# buck.net
KiCad netlist of a schematic drawn in Altium Designer
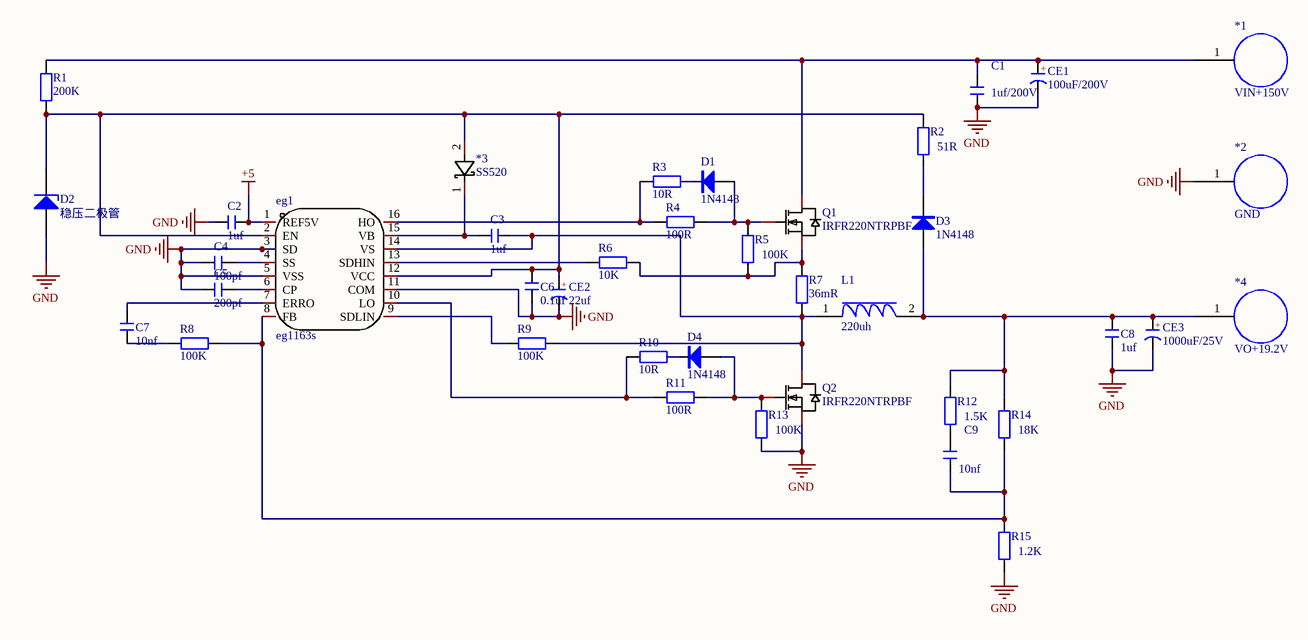
[diagram p0: buck.SchDoc]

(export (version "E")
  (design (tool "Eeschema 10.0.6"))
  (components
    (comp (ref "*1") (value "VIN+150V") (footprint "焊盘接口") (libsource (lib "buck") (part "焊盘接口")))
    (comp (ref "*2") (value "GND") (footprint "焊盘接口") (libsource (lib "buck") (part "焊盘接口")))
    (comp (ref "*3") (value "SS520") (footprint "SS520") (libsource (lib "buck") (part "SS520")))
    (comp (ref "*4") (value "VO+19.2V") (footprint "焊盘接口") (libsource (lib "buck") (part "焊盘接口")))
    (comp (ref "C1")
      (value "1uf/200V")
      (footprint "C 0603_L")
      (description "贴片电容")
      (libsource (lib "0.1 - 电阻-电容-电感") (part "C"))
    )
    (comp (ref "C2")
      (value "1uf")
      (footprint "C 0603_L")
      (description "贴片电容")
      (libsource (lib "0.1 - 电阻-电容-电感") (part "C"))
    )
    (comp (ref "C3")
      (value "1uf")
      (footprint "C 0603_L")
      (description "贴片电容")
      (libsource (lib "0.1 - 电阻-电容-电感") (part "C"))
    )
    (comp (ref "C4")
      (value "100pf")
      (footprint "C 0603_L")
      (description "贴片电容")
      (libsource (lib "0.1 - 电阻-电容-电感") (part "C"))
    )
    (comp (ref "C5")
      (value "200pf")
      (footprint "C 0603_L")
      (description "贴片电容")
      (libsource (lib "0.1 - 电阻-电容-电感") (part "C"))
    )
    (comp (ref "C6")
      (value "0.1uf")
      (footprint "C 0603_L")
      (description "贴片电容")
      (libsource (lib "0.1 - 电阻-电容-电感") (part "C"))
    )
    (comp (ref "C7")
      (value "10nf")
      (footprint "C 0603_L")
      (description "贴片电容")
      (libsource (lib "0.1 - 电阻-电容-电感") (part "C"))
    )
    (comp (ref "C8")
      (value "1uf")
      (footprint "C 0603_L")
      (description "贴片电容")
      (libsource (lib "0.1 - 电阻-电容-电感") (part "C"))
    )
    (comp (ref "C9")
      (value "10nf")
      (footprint "C 0603_L")
      (description "贴片电容")
      (libsource (lib "0.1 - 电阻-电容-电感") (part "C"))
    )
    (comp (ref "CE1")
      (value "100uF/200V")
      (footprint "CAP 10*22*40 - GD")
      (description "直插电解电容")
      (libsource (lib "0.1 - 电阻-电容-电感") (part "CE"))
    )
    (comp (ref "CE2")
      (value "22uf")
      (footprint "CAP 10*22*31.5")
      (description "直插电解电容")
      (libsource (lib "0.1 - 电阻-电容-电感") (part "CE"))
    )
    (comp (ref "CE3")
      (value "1000uF/25V")
      (footprint "CAP 10*22*31.5")
      (description "直插电解电容")
      (libsource (lib "0.1 - 电阻-电容-电感") (part "CE"))
    )
    (comp (ref "D1")
      (value "1N4148")
      (footprint "MINI_MELF (LL34)")
      (description "开关二极管")
      (libsource (lib "0.2 - 二极管-整流桥") (part "1N4148"))
    )
    (comp (ref "D2")
      (value "稳压二极管")
      (footprint "SOD-123")
      (description "Zener Diode")
      (libsource (lib "0.2 - 二极管-整流桥") (part "稳压二极管"))
    )
    (comp (ref "D3")
      (value "1N4148")
      (footprint "MINI_MELF (LL34)")
      (description "开关二极管")
      (libsource (lib "0.2 - 二极管-整流桥") (part "1N4148"))
    )
    (comp (ref "D4")
      (value "1N4148")
      (footprint "MINI_MELF (LL34)")
      (description "开关二极管")
      (libsource (lib "0.2 - 二极管-整流桥") (part "1N4148"))
    )
    (comp (ref "eg1") (value "eg1163s") (footprint "eg1163S") (libsource (lib "Schlib1") (part "eg1163s")))
    (comp (ref "L1") (value "220uh") (footprint "电感") (libsource (lib "buck") (part "电感")))
    (comp (ref "Q1")
      (value "IRFR220NTRPBF")
      (footprint "IRFR220NTRPBF")
      (fields (field (name "MANUFACTURER") "Infineon(英飞凌)") (field (name "NAME") "IRFR220NTRPBF"))
      (libsource (lib "buck") (part "IRFR220NTRPBF"))
    )
    (comp (ref "Q2")
      (value "IRFR220NTRPBF")
      (footprint "IRFR220NTRPBF")
      (fields (field (name "MANUFACTURER") "Infineon(英飞凌)") (field (name "NAME") "IRFR220NTRPBF"))
      (libsource (lib "buck") (part "IRFR220NTRPBF"))
    )
    (comp (ref "R1")
      (value "200K")
      (footprint "RES 0603")
      (description "贴片电阻")
      (fields (field (name "版权归属") "来自淘宝 ID：黄晶宝石"))
      (libsource (lib "0.1 - 电阻-电容-电感") (part "R"))
    )
    (comp (ref "R2")
      (value "51R")
      (footprint "RES 0603")
      (description "贴片电阻")
      (fields (field (name "版权归属") "来自淘宝 ID：黄晶宝石"))
      (libsource (lib "0.1 - 电阻-电容-电感") (part "R"))
    )
    (comp (ref "R3")
      (value "10R")
      (footprint "RES 0603")
      (description "贴片电阻")
      (fields (field (name "版权归属") "来自淘宝 ID：黄晶宝石"))
      (libsource (lib "0.1 - 电阻-电容-电感") (part "R"))
    )
    (comp (ref "R4")
      (value "100R")
      (footprint "RES 0603")
      (description "贴片电阻")
      (fields (field (name "版权归属") "来自淘宝 ID：黄晶宝石"))
      (libsource (lib "0.1 - 电阻-电容-电感") (part "R"))
    )
    (comp (ref "R5")
      (value "100K")
      (footprint "RES 0603")
      (description "贴片电阻")
      (fields (field (name "版权归属") "来自淘宝 ID：黄晶宝石"))
      (libsource (lib "0.1 - 电阻-电容-电感") (part "R"))
    )
    (comp (ref "R6")
      (value "10K")
      (footprint "RES 0603")
      (description "贴片电阻")
      (fields (field (name "版权归属") "来自淘宝 ID：黄晶宝石"))
      (libsource (lib "0.1 - 电阻-电容-电感") (part "R"))
    )
    (comp (ref "R7")
      (value "36mR")
      (footprint "RES 0603")
      (description "贴片电阻")
      (fields (field (name "版权归属") "来自淘宝 ID：黄晶宝石"))
      (libsource (lib "0.1 - 电阻-电容-电感") (part "R"))
    )
    (comp (ref "R8")
      (value "100K")
      (footprint "RES 0603")
      (description "贴片电阻")
      (fields (field (name "版权归属") "来自淘宝 ID：黄晶宝石"))
      (libsource (lib "0.1 - 电阻-电容-电感") (part "R"))
    )
    (comp (ref "R9")
      (value "100K")
      (footprint "RES 0603")
      (description "贴片电阻")
      (fields (field (name "版权归属") "来自淘宝 ID：黄晶宝石"))
      (libsource (lib "0.1 - 电阻-电容-电感") (part "R"))
    )
    (comp (ref "R10")
      (value "10R")
      (footprint "RES 0603")
      (description "贴片电阻")
      (fields (field (name "版权归属") "来自淘宝 ID：黄晶宝石"))
      (libsource (lib "0.1 - 电阻-电容-电感") (part "R"))
    )
    (comp (ref "R11")
      (value "100R")
      (footprint "RES 0603")
      (description "贴片电阻")
      (fields (field (name "版权归属") "来自淘宝 ID：黄晶宝石"))
      (libsource (lib "0.1 - 电阻-电容-电感") (part "R"))
    )
    (comp (ref "R12")
      (value "1.5K")
      (footprint "RES 0603")
      (description "贴片电阻")
      (fields (field (name "版权归属") "来自淘宝 ID：黄晶宝石"))
      (libsource (lib "0.1 - 电阻-电容-电感") (part "R"))
    )
    (comp (ref "R13")
      (value "100K")
      (footprint "RES 0603")
      (description "贴片电阻")
      (fields (field (name "版权归属") "来自淘宝 ID：黄晶宝石"))
      (libsource (lib "0.1 - 电阻-电容-电感") (part "R"))
    )
    (comp (ref "R14")
      (value "18K")
      (footprint "RES 0603")
      (description "贴片电阻")
      (fields (field (name "版权归属") "来自淘宝 ID：黄晶宝石"))
      (libsource (lib "0.1 - 电阻-电容-电感") (part "R"))
    )
    (comp (ref "R15")
      (value "1.2K")
      (footprint "RES 0603")
      (description "贴片电阻")
      (fields (field (name "版权归属") "来自淘宝 ID：黄晶宝石"))
      (libsource (lib "0.1 - 电阻-电容-电感") (part "R"))
    )
  )
  (nets
    (net (code "1") (name "+5") (class "Default")
      (node (ref "C2") (pin "2") (pinfunction "2_2") (pintype "passive"))
      (node (ref "eg1") (pin "1") (pinfunction "REF5V_1") (pintype "passive"))
    )
    (net (code "2") (name "GND") (class "Default")
      (node (ref "*2") (pin "1") (pinfunction "1_1") (pintype "passive"))
      (node (ref "C1") (pin "1") (pinfunction "1_1") (pintype "passive"))
      (node (ref "C2") (pin "1") (pinfunction "1_1") (pintype "passive"))
      (node (ref "C4") (pin "1") (pinfunction "1_1") (pintype "passive"))
      (node (ref "C5") (pin "1") (pinfunction "1_1") (pintype "passive"))
      (node (ref "C6") (pin "2") (pinfunction "2_2") (pintype "passive"))
      (node (ref "C8") (pin "1") (pinfunction "1_1") (pintype "passive"))
      (node (ref "CE1") (pin "2") (pinfunction "K_2") (pintype "passive"))
      (node (ref "CE2") (pin "2") (pinfunction "K_2") (pintype "passive"))
      (node (ref "CE3") (pin "2") (pinfunction "K_2") (pintype "passive"))
      (node (ref "D2") (pin "1") (pinfunction "A_1") (pintype "passive"))
      (node (ref "Q2") (pin "3") (pinfunction "S_3") (pintype "passive"))
      (node (ref "R13") (pin "2") (pinfunction "2_2") (pintype "passive"))
      (node (ref "R15") (pin "2") (pinfunction "2_2") (pintype "passive"))
      (node (ref "eg1") (pin "11") (pinfunction "COM_11") (pintype "passive"))
      (node (ref "eg1") (pin "3") (pinfunction "SD_3") (pintype "passive"))
      (node (ref "eg1") (pin "5") (pinfunction "VSS_5") (pintype "passive"))
    )
    (net (code "3") (name "Net-(*3-A)") (class "Default")
      (node (ref "*3") (pin "2") (pinfunction "A_2") (pintype "passive"))
      (node (ref "C6") (pin "1") (pinfunction "1_1") (pintype "passive"))
      (node (ref "CE2") (pin "1") (pinfunction "A_1") (pintype "passive"))
      (node (ref "D2") (pin "2") (pinfunction "K_2") (pintype "passive"))
      (node (ref "R1") (pin "1") (pinfunction "1_1") (pintype "passive"))
      (node (ref "R2") (pin "1") (pinfunction "1_1") (pintype "passive"))
      (node (ref "eg1") (pin "12") (pinfunction "VCC_12") (pintype "passive"))
      (node (ref "eg1") (pin "2") (pinfunction "EN_2") (pintype "passive"))
    )
    (net (code "4") (name "Net-(*3-K)") (class "Default")
      (node (ref "*3") (pin "1") (pinfunction "K_1") (pintype "passive"))
      (node (ref "C3") (pin "2") (pinfunction "2_2") (pintype "passive"))
      (node (ref "eg1") (pin "15") (pinfunction "VB_15") (pintype "passive"))
    )
    (net (code "5") (name "Net-(C7-Pad1)") (class "Default")
      (node (ref "C7") (pin "1") (pinfunction "1_1") (pintype "passive"))
      (node (ref "R8") (pin "2") (pinfunction "2_2") (pintype "passive"))
    )
    (net (code "6") (name "Net-(C9-Pad2)") (class "Default")
      (node (ref "C9") (pin "2") (pinfunction "2_2") (pintype "passive"))
      (node (ref "R12") (pin "2") (pinfunction "2_2") (pintype "passive"))
    )
    (net (code "7") (name "Net-(CE1-A)") (class "Default")
      (node (ref "*1") (pin "1") (pinfunction "1_1") (pintype "passive"))
      (node (ref "C1") (pin "2") (pinfunction "2_2") (pintype "passive"))
      (node (ref "CE1") (pin "1") (pinfunction "A_1") (pintype "passive"))
      (node (ref "Q1") (pin "2") (pinfunction "D_2") (pintype "passive"))
      (node (ref "R1") (pin "2") (pinfunction "2_2") (pintype "passive"))
    )
    (net (code "8") (name "Net-(CE3-A)") (class "Default")
      (node (ref "*4") (pin "1") (pinfunction "1_1") (pintype "passive"))
      (node (ref "C8") (pin "2") (pinfunction "2_2") (pintype "passive"))
      (node (ref "CE3") (pin "1") (pinfunction "A_1") (pintype "passive"))
      (node (ref "D3") (pin "1") (pinfunction "A_1") (pintype "passive"))
      (node (ref "L1") (pin "2") (pinfunction "2_2") (pintype "passive"))
      (node (ref "R12") (pin "1") (pinfunction "1_1") (pintype "passive"))
      (node (ref "R14") (pin "1") (pinfunction "1_1") (pintype "passive"))
    )
    (net (code "9") (name "Net-(D1-A)") (class "Default")
      (node (ref "D1") (pin "1") (pinfunction "A_1") (pintype "passive"))
      (node (ref "Q1") (pin "1") (pinfunction "G_1") (pintype "passive"))
      (node (ref "R4") (pin "1") (pinfunction "1_1") (pintype "passive"))
      (node (ref "R5") (pin "1") (pinfunction "1_1") (pintype "passive"))
    )
    (net (code "10") (name "Net-(D1-K)") (class "Default")
      (node (ref "D1") (pin "2") (pinfunction "K_2") (pintype "passive"))
      (node (ref "R3") (pin "1") (pinfunction "1_1") (pintype "passive"))
    )
    (net (code "11") (name "Net-(D3-K)") (class "Default")
      (node (ref "D3") (pin "2") (pinfunction "K_2") (pintype "passive"))
      (node (ref "R2") (pin "2") (pinfunction "2_2") (pintype "passive"))
    )
    (net (code "12") (name "Net-(D4-A)") (class "Default")
      (node (ref "D4") (pin "1") (pinfunction "A_1") (pintype "passive"))
      (node (ref "Q2") (pin "1") (pinfunction "G_1") (pintype "passive"))
      (node (ref "R11") (pin "1") (pinfunction "1_1") (pintype "passive"))
      (node (ref "R13") (pin "1") (pinfunction "1_1") (pintype "passive"))
    )
    (net (code "13") (name "Net-(D4-K)") (class "Default")
      (node (ref "D4") (pin "2") (pinfunction "K_2") (pintype "passive"))
      (node (ref "R10") (pin "1") (pinfunction "1_1") (pintype "passive"))
    )
    (net (code "14") (name "Net-(Q1-S)") (class "Default")
      (node (ref "Q1") (pin "3") (pinfunction "S_3") (pintype "passive"))
      (node (ref "R5") (pin "2") (pinfunction "2_2") (pintype "passive"))
      (node (ref "R6") (pin "1") (pinfunction "1_1") (pintype "passive"))
      (node (ref "R7") (pin "1") (pinfunction "1_1") (pintype "passive"))
    )
    (net (code "15") (name "Net-(Q2-D)") (class "Default")
      (node (ref "C3") (pin "1") (pinfunction "1_1") (pintype "passive"))
      (node (ref "L1") (pin "1") (pinfunction "1_1") (pintype "passive"))
      (node (ref "Q2") (pin "2") (pinfunction "D_2") (pintype "passive"))
      (node (ref "R7") (pin "2") (pinfunction "2_2") (pintype "passive"))
      (node (ref "R9") (pin "1") (pinfunction "1_1") (pintype "passive"))
      (node (ref "eg1") (pin "14") (pinfunction "VS_14") (pintype "passive"))
    )
    (net (code "16") (name "Net-(eg1-CP)") (class "Default")
      (node (ref "C5") (pin "2") (pinfunction "2_2") (pintype "passive"))
      (node (ref "eg1") (pin "6") (pinfunction "CP_6") (pintype "passive"))
    )
    (net (code "17") (name "Net-(eg1-ERRO)") (class "Default")
      (node (ref "C7") (pin "2") (pinfunction "2_2") (pintype "passive"))
      (node (ref "eg1") (pin "7") (pinfunction "ERRO_7") (pintype "passive"))
    )
    (net (code "18") (name "Net-(eg1-FB)") (class "Default")
      (node (ref "C9") (pin "1") (pinfunction "1_1") (pintype "passive"))
      (node (ref "R14") (pin "2") (pinfunction "2_2") (pintype "passive"))
      (node (ref "R15") (pin "1") (pinfunction "1_1") (pintype "passive"))
      (node (ref "R8") (pin "1") (pinfunction "1_1") (pintype "passive"))
      (node (ref "eg1") (pin "8") (pinfunction "FB_8") (pintype "passive"))
    )
    (net (code "19") (name "Net-(eg1-HO)") (class "Default")
      (node (ref "R3") (pin "2") (pinfunction "2_2") (pintype "passive"))
      (node (ref "R4") (pin "2") (pinfunction "2_2") (pintype "passive"))
      (node (ref "eg1") (pin "16") (pinfunction "HO_16") (pintype "passive"))
    )
    (net (code "20") (name "Net-(eg1-LO)") (class "Default")
      (node (ref "R10") (pin "2") (pinfunction "2_2") (pintype "passive"))
      (node (ref "R11") (pin "2") (pinfunction "2_2") (pintype "passive"))
      (node (ref "eg1") (pin "10") (pinfunction "LO_10") (pintype "passive"))
    )
    (net (code "21") (name "Net-(eg1-SDHIN)") (class "Default")
      (node (ref "R6") (pin "2") (pinfunction "2_2") (pintype "passive"))
      (node (ref "eg1") (pin "13") (pinfunction "SDHIN_13") (pintype "passive"))
    )
    (net (code "22") (name "Net-(eg1-SDLIN)") (class "Default")
      (node (ref "R9") (pin "2") (pinfunction "2_2") (pintype "passive"))
      (node (ref "eg1") (pin "9") (pinfunction "SDLIN_9") (pintype "passive"))
    )
    (net (code "23") (name "Net-(eg1-SS)") (class "Default")
      (node (ref "C4") (pin "2") (pinfunction "2_2") (pintype "passive"))
      (node (ref "eg1") (pin "4") (pinfunction "SS_4") (pintype "passive"))
    )
  )
)
